# sevenSeg4_atmega_4C_noGND.net
KiCad netlist of a schematic drawn in EAGLE
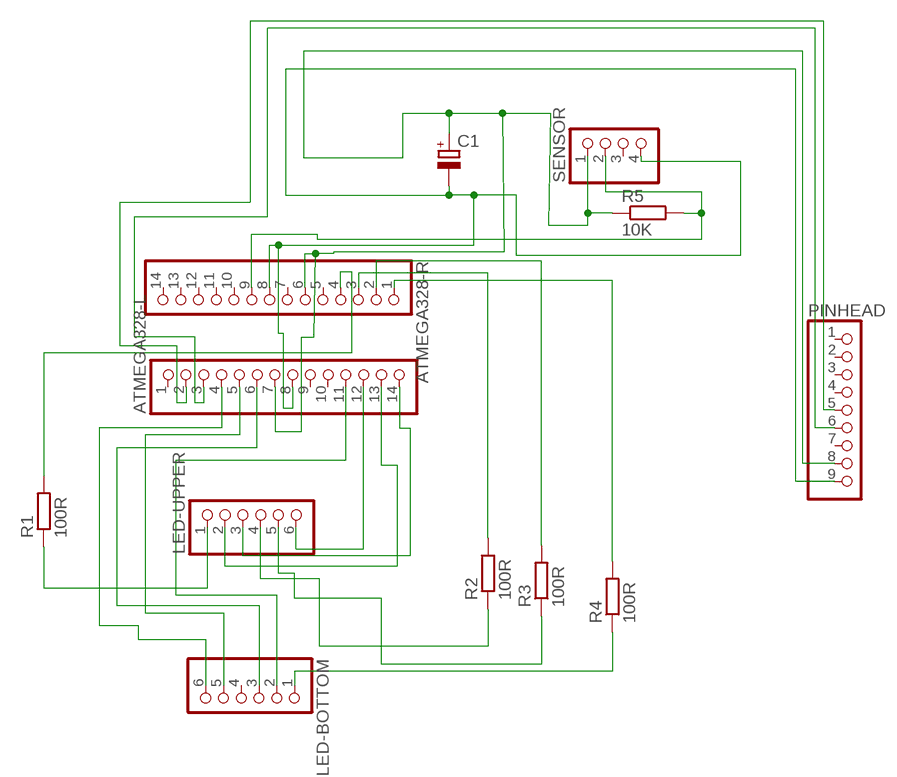
[diagram p0: schematic, sheet 1]

(export (version "E")
  (design (tool "Eeschema 10.0.6"))
  (components
    (comp (ref "ATMEGA328-L")
      (value "PINHD-1X14")
      (footprint "eagle-import:1X14")
      (libsource (lib "eagle-import") (part "PINHD-1X14"))
    )
    (comp (ref "ATMEGA328-R")
      (value "PINHD-1X14")
      (footprint "eagle-import:1X14")
      (libsource (lib "eagle-import") (part "PINHD-1X14"))
    )
    (comp (ref "C1")
      (value "CPOL-EUE2.5-7")
      (footprint "eagle-import:E2,5-7")
      (libsource (lib "eagle-import") (part "CPOL-EUE2.5-7"))
    )
    (comp (ref "LED-BOTTOM")
      (value "PINHD-1X6")
      (footprint "eagle-import:1X06")
      (libsource (lib "eagle-import") (part "PINHD-1X6"))
    )
    (comp (ref "LED-UPPER")
      (value "PINHD-1X6")
      (footprint "eagle-import:1X06")
      (libsource (lib "eagle-import") (part "PINHD-1X6"))
    )
    (comp (ref "PINHEAD")
      (value "PINHD-1X9")
      (footprint "eagle-import:1X09")
      (libsource (lib "eagle-import") (part "PINHD-1X9"))
    )
    (comp (ref "R1")
      (value "100R")
      (footprint "eagle-import:R0603")
      (libsource (lib "eagle-import") (part "R-EU_R0603"))
    )
    (comp (ref "R2")
      (value "100R")
      (footprint "eagle-import:R0603")
      (libsource (lib "eagle-import") (part "R-EU_R0603"))
    )
    (comp (ref "R3")
      (value "100R")
      (footprint "eagle-import:R0603")
      (libsource (lib "eagle-import") (part "R-EU_R0603"))
    )
    (comp (ref "R4")
      (value "100R")
      (footprint "eagle-import:R0603")
      (libsource (lib "eagle-import") (part "R-EU_R0603"))
    )
    (comp (ref "R5")
      (value "10K")
      (footprint "eagle-import:R0603")
      (libsource (lib "eagle-import") (part "R-EU_R0603"))
    )
    (comp (ref "SENSOR")
      (value "PINHD-1X4")
      (footprint "eagle-import:1X04")
      (libsource (lib "eagle-import") (part "PINHD-1X4"))
    )
  )
  (nets
    (net (code "1") (name "Net-(ATMEGA328-L-Pad2)") (class "Default")
      (node (ref "ATMEGA328-L") (pin "2") (pinfunction "2_2") (pintype "passive"))
      (node (ref "PINHEAD") (pin "5") (pinfunction "5_5") (pintype "passive"))
    )
    (net (code "2") (name "Net-(ATMEGA328-L-Pad3)") (class "Default")
      (node (ref "ATMEGA328-L") (pin "3") (pinfunction "3_3") (pintype "passive"))
      (node (ref "PINHEAD") (pin "6") (pinfunction "6_6") (pintype "passive"))
    )
    (net (code "3") (name "Net-(ATMEGA328-L-Pad4)") (class "Default")
      (node (ref "ATMEGA328-L") (pin "4") (pinfunction "4_4") (pintype "passive"))
      (node (ref "LED-BOTTOM") (pin "6") (pinfunction "6_6") (pintype "passive"))
    )
    (net (code "4") (name "Net-(ATMEGA328-L-Pad5)") (class "Default")
      (node (ref "ATMEGA328-L") (pin "5") (pinfunction "5_5") (pintype "passive"))
      (node (ref "LED-BOTTOM") (pin "5") (pinfunction "5_5") (pintype "passive"))
    )
    (net (code "5") (name "Net-(ATMEGA328-L-Pad6)") (class "Default")
      (node (ref "ATMEGA328-L") (pin "6") (pinfunction "6_6") (pintype "passive"))
      (node (ref "LED-BOTTOM") (pin "3") (pinfunction "3_3") (pintype "passive"))
    )
    (net (code "6") (name "Net-(ATMEGA328-L-Pad7)") (class "Default")
      (node (ref "ATMEGA328-L") (pin "7") (pinfunction "7_7") (pintype "passive"))
      (node (ref "ATMEGA328-R") (pin "6") (pinfunction "6_6") (pintype "passive"))
      (node (ref "C1") (pin "+") (pinfunction "+_+") (pintype "passive"))
      (node (ref "PINHEAD") (pin "8") (pinfunction "8_8") (pintype "passive"))
      (node (ref "R5") (pin "1") (pinfunction "1_1") (pintype "passive"))
      (node (ref "SENSOR") (pin "1") (pinfunction "1_1") (pintype "passive"))
    )
    (net (code "7") (name "Net-(ATMEGA328-L-Pad8)") (class "Default")
      (node (ref "ATMEGA328-L") (pin "8") (pinfunction "8_8") (pintype "passive"))
      (node (ref "ATMEGA328-R") (pin "8") (pinfunction "8_8") (pintype "passive"))
      (node (ref "C1") (pin "-") (pinfunction "-_-") (pintype "passive"))
      (node (ref "PINHEAD") (pin "9") (pinfunction "9_9") (pintype "passive"))
      (node (ref "SENSOR") (pin "4") (pinfunction "4_4") (pintype "passive"))
    )
    (net (code "8") (name "Net-(ATMEGA328-L-Pad11)") (class "Default")
      (node (ref "ATMEGA328-L") (pin "11") (pinfunction "11_11") (pintype "passive"))
      (node (ref "LED-BOTTOM") (pin "2") (pinfunction "2_2") (pintype "passive"))
    )
    (net (code "9") (name "Net-(ATMEGA328-L-Pad12)") (class "Default")
      (node (ref "ATMEGA328-L") (pin "12") (pinfunction "12_12") (pintype "passive"))
      (node (ref "LED-UPPER") (pin "6") (pinfunction "6_6") (pintype "passive"))
    )
    (net (code "10") (name "Net-(ATMEGA328-L-Pad13)") (class "Default")
      (node (ref "ATMEGA328-L") (pin "13") (pinfunction "13_13") (pintype "passive"))
      (node (ref "LED-UPPER") (pin "2") (pinfunction "2_2") (pintype "passive"))
    )
    (net (code "11") (name "Net-(ATMEGA328-L-Pad14)") (class "Default")
      (node (ref "ATMEGA328-L") (pin "14") (pinfunction "14_14") (pintype "passive"))
      (node (ref "LED-UPPER") (pin "3") (pinfunction "3_3") (pintype "passive"))
    )
    (net (code "12") (name "Net-(ATMEGA328-R-Pad1)") (class "Default")
      (node (ref "ATMEGA328-R") (pin "1") (pinfunction "1_1") (pintype "passive"))
      (node (ref "R4") (pin "2") (pinfunction "2_2") (pintype "passive"))
    )
    (net (code "13") (name "Net-(ATMEGA328-R-Pad2)") (class "Default")
      (node (ref "ATMEGA328-R") (pin "2") (pinfunction "2_2") (pintype "passive"))
      (node (ref "R3") (pin "2") (pinfunction "2_2") (pintype "passive"))
    )
    (net (code "14") (name "Net-(ATMEGA328-R-Pad3)") (class "Default")
      (node (ref "ATMEGA328-R") (pin "3") (pinfunction "3_3") (pintype "passive"))
      (node (ref "R2") (pin "2") (pinfunction "2_2") (pintype "passive"))
    )
    (net (code "15") (name "Net-(ATMEGA328-R-Pad4)") (class "Default")
      (node (ref "ATMEGA328-R") (pin "4") (pinfunction "4_4") (pintype "passive"))
      (node (ref "R1") (pin "2") (pinfunction "2_2") (pintype "passive"))
    )
    (net (code "16") (name "Net-(ATMEGA328-R-Pad9)") (class "Default")
      (node (ref "ATMEGA328-R") (pin "9") (pinfunction "9_9") (pintype "passive"))
      (node (ref "R5") (pin "2") (pinfunction "2_2") (pintype "passive"))
      (node (ref "SENSOR") (pin "2") (pinfunction "2_2") (pintype "passive"))
    )
    (net (code "17") (name "Net-(LED-BOTTOM-Pad1)") (class "Default")
      (node (ref "LED-BOTTOM") (pin "1") (pinfunction "1_1") (pintype "passive"))
      (node (ref "R4") (pin "1") (pinfunction "1_1") (pintype "passive"))
    )
    (net (code "18") (name "Net-(LED-UPPER-Pad1)") (class "Default")
      (node (ref "LED-UPPER") (pin "1") (pinfunction "1_1") (pintype "passive"))
      (node (ref "R1") (pin "1") (pinfunction "1_1") (pintype "passive"))
    )
    (net (code "19") (name "Net-(LED-UPPER-Pad4)") (class "Default")
      (node (ref "LED-UPPER") (pin "4") (pinfunction "4_4") (pintype "passive"))
      (node (ref "R2") (pin "1") (pinfunction "1_1") (pintype "passive"))
    )
    (net (code "20") (name "Net-(LED-UPPER-Pad5)") (class "Default")
      (node (ref "LED-UPPER") (pin "5") (pinfunction "5_5") (pintype "passive"))
      (node (ref "R3") (pin "1") (pinfunction "1_1") (pintype "passive"))
    )
    (net (code "21") (name "unconnected-(ATMEGA328-L-Pad1)") (class "Default")
      (node (ref "ATMEGA328-L") (pin "1") (pinfunction "1_1") (pintype "passive"))
    )
    (net (code "22") (name "unconnected-(ATMEGA328-L-Pad9)") (class "Default")
      (node (ref "ATMEGA328-L") (pin "9") (pinfunction "9_9") (pintype "passive"))
    )
    (net (code "23") (name "unconnected-(ATMEGA328-L-Pad10)") (class "Default")
      (node (ref "ATMEGA328-L") (pin "10") (pinfunction "10_10") (pintype "passive"))
    )
    (net (code "24") (name "unconnected-(ATMEGA328-R-Pad5)") (class "Default")
      (node (ref "ATMEGA328-R") (pin "5") (pinfunction "5_5") (pintype "passive"))
    )
    (net (code "25") (name "unconnected-(ATMEGA328-R-Pad7)") (class "Default")
      (node (ref "ATMEGA328-R") (pin "7") (pinfunction "7_7") (pintype "passive"))
    )
    (net (code "26") (name "unconnected-(ATMEGA328-R-Pad10)") (class "Default")
      (node (ref "ATMEGA328-R") (pin "10") (pinfunction "10_10") (pintype "passive"))
    )
    (net (code "27") (name "unconnected-(ATMEGA328-R-Pad11)") (class "Default")
      (node (ref "ATMEGA328-R") (pin "11") (pinfunction "11_11") (pintype "passive"))
    )
    (net (code "28") (name "unconnected-(ATMEGA328-R-Pad12)") (class "Default")
      (node (ref "ATMEGA328-R") (pin "12") (pinfunction "12_12") (pintype "passive"))
    )
    (net (code "29") (name "unconnected-(ATMEGA328-R-Pad13)") (class "Default")
      (node (ref "ATMEGA328-R") (pin "13") (pinfunction "13_13") (pintype "passive"))
    )
    (net (code "30") (name "unconnected-(ATMEGA328-R-Pad14)") (class "Default")
      (node (ref "ATMEGA328-R") (pin "14") (pinfunction "14_14") (pintype "passive"))
    )
    (net (code "31") (name "unconnected-(LED-BOTTOM-Pad4)") (class "Default")
      (node (ref "LED-BOTTOM") (pin "4") (pinfunction "4_4") (pintype "passive"))
    )
    (net (code "32") (name "unconnected-(PINHEAD-Pad1)") (class "Default")
      (node (ref "PINHEAD") (pin "1") (pinfunction "1_1") (pintype "passive"))
    )
    (net (code "33") (name "unconnected-(PINHEAD-Pad2)") (class "Default")
      (node (ref "PINHEAD") (pin "2") (pinfunction "2_2") (pintype "passive"))
    )
    (net (code "34") (name "unconnected-(PINHEAD-Pad3)") (class "Default")
      (node (ref "PINHEAD") (pin "3") (pinfunction "3_3") (pintype "passive"))
    )
    (net (code "35") (name "unconnected-(PINHEAD-Pad4)") (class "Default")
      (node (ref "PINHEAD") (pin "4") (pinfunction "4_4") (pintype "passive"))
    )
    (net (code "36") (name "unconnected-(PINHEAD-Pad7)") (class "Default")
      (node (ref "PINHEAD") (pin "7") (pinfunction "7_7") (pintype "passive"))
    )
    (net (code "37") (name "unconnected-(SENSOR-Pad3)") (class "Default")
      (node (ref "SENSOR") (pin "3") (pinfunction "3_3") (pintype "passive"))
    )
  )
)
